# 24V_AC_SSR_Board.net
KiCad netlist of a schematic drawn in EAGLE
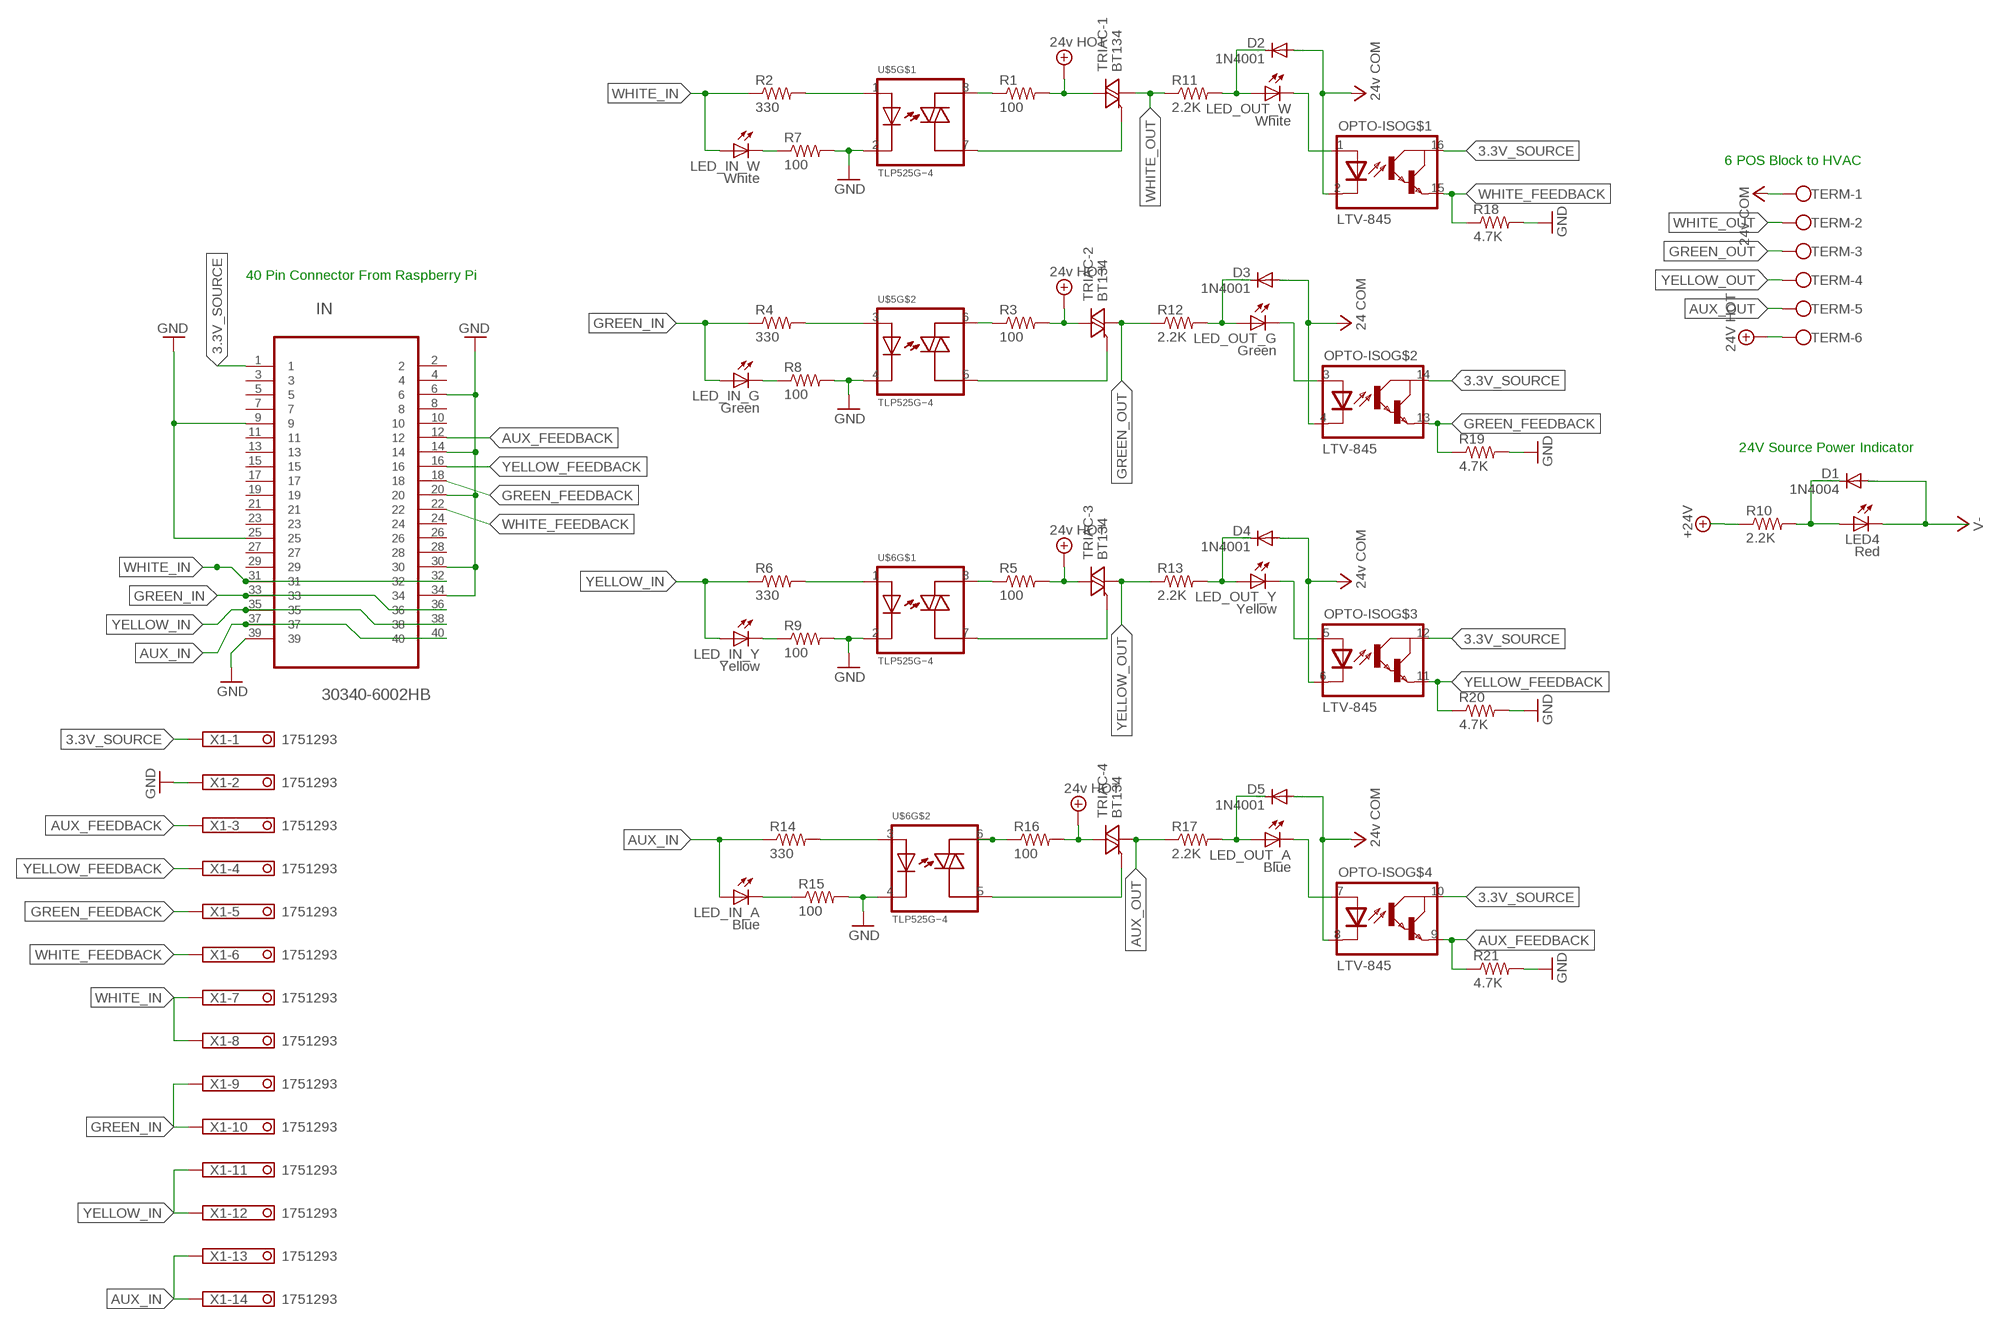
[diagram p0: schematic, sheet 1]

(export (version "E")
  (design (tool "Eeschema 10.0.6"))
  (components
    (comp (ref "D1")
      (value "1N4004")
      (footprint "eagle-import:DO41-10")
      (libsource (lib "eagle-import") (part "1N4004"))
    )
    (comp (ref "D2")
      (value "1N4001")
      (footprint "eagle-import:DO41-10")
      (libsource (lib "eagle-import") (part "1N4004"))
    )
    (comp (ref "D3")
      (value "1N4001")
      (footprint "eagle-import:DO41-10")
      (libsource (lib "eagle-import") (part "1N4004"))
    )
    (comp (ref "D4")
      (value "1N4001")
      (footprint "eagle-import:DO41-10")
      (libsource (lib "eagle-import") (part "1N4004"))
    )
    (comp (ref "D5")
      (value "1N4001")
      (footprint "eagle-import:DO41-10")
      (libsource (lib "eagle-import") (part "1N4004"))
    )
    (comp (ref "IN")
      (value "30340-6002HB")
      (footprint "eagle-import:3M_2540-6002UB")
      (fields (field (name "MPN") "2540-6002UB"))
      (libsource (lib "eagle-import") (part "2540-6002UB"))
    )
    (comp (ref "LED4")
      (value "Red")
      (footprint "eagle-import:LED3MM")
      (libsource (lib "eagle-import") (part "LED3MM"))
    )
    (comp (ref "LED_IN_A")
      (value "Blue")
      (footprint "eagle-import:LED3MM")
      (libsource (lib "eagle-import") (part "LED3MM"))
    )
    (comp (ref "LED_IN_G")
      (value "Green")
      (footprint "eagle-import:LED3MM")
      (libsource (lib "eagle-import") (part "LED3MM"))
    )
    (comp (ref "LED_IN_W")
      (value "White")
      (footprint "eagle-import:LED3MM")
      (libsource (lib "eagle-import") (part "LED3MM"))
    )
    (comp (ref "LED_IN_Y")
      (value "Yellow")
      (footprint "eagle-import:LED3MM")
      (libsource (lib "eagle-import") (part "LED3MM"))
    )
    (comp (ref "LED_OUT_A")
      (value "Blue")
      (footprint "eagle-import:LED3MM")
      (libsource (lib "eagle-import") (part "LED3MM"))
    )
    (comp (ref "LED_OUT_G")
      (value "Green")
      (footprint "eagle-import:LED3MM")
      (libsource (lib "eagle-import") (part "LED3MM"))
    )
    (comp (ref "LED_OUT_W")
      (value "White")
      (footprint "eagle-import:LED3MM")
      (libsource (lib "eagle-import") (part "LED3MM"))
    )
    (comp (ref "LED_OUT_Y")
      (value "Yellow")
      (footprint "eagle-import:LED3MM")
      (libsource (lib "eagle-import") (part "LED3MM"))
    )
    (comp (ref "OPTO-ISO")
      (value "LTV-845")
      (footprint "eagle-import:DIL16")
      (libsource (lib "eagle-import") (part "LTV-845"))
    )
    (comp (ref "R1")
      (value "100")
      (footprint "eagle-import:0204_7")
      (libsource (lib "eagle-import") (part "R-US_0204/7"))
    )
    (comp (ref "R2")
      (value "330")
      (footprint "eagle-import:0204_7")
      (libsource (lib "eagle-import") (part "R-US_0204/7"))
    )
    (comp (ref "R3")
      (value "100")
      (footprint "eagle-import:0204_7")
      (libsource (lib "eagle-import") (part "R-US_0204/7"))
    )
    (comp (ref "R4")
      (value "330")
      (footprint "eagle-import:0204_7")
      (libsource (lib "eagle-import") (part "R-US_0204/7"))
    )
    (comp (ref "R5")
      (value "100")
      (footprint "eagle-import:0204_7")
      (libsource (lib "eagle-import") (part "R-US_0204/7"))
    )
    (comp (ref "R6")
      (value "330")
      (footprint "eagle-import:0204_7")
      (libsource (lib "eagle-import") (part "R-US_0204/7"))
    )
    (comp (ref "R7")
      (value "100")
      (footprint "eagle-import:0204_7")
      (libsource (lib "eagle-import") (part "R-US_0204/7"))
    )
    (comp (ref "R8")
      (value "100")
      (footprint "eagle-import:0204_7")
      (libsource (lib "eagle-import") (part "R-US_0204/7"))
    )
    (comp (ref "R9")
      (value "100")
      (footprint "eagle-import:0204_7")
      (libsource (lib "eagle-import") (part "R-US_0204/7"))
    )
    (comp (ref "R10")
      (value "2.2K")
      (footprint "eagle-import:0204_7")
      (libsource (lib "eagle-import") (part "R-US_0204/7"))
    )
    (comp (ref "R11")
      (value "2.2K")
      (footprint "eagle-import:0204_7")
      (libsource (lib "eagle-import") (part "R-US_0204/7"))
    )
    (comp (ref "R12")
      (value "2.2K")
      (footprint "eagle-import:0204_7")
      (libsource (lib "eagle-import") (part "R-US_0204/7"))
    )
    (comp (ref "R13")
      (value "2.2K")
      (footprint "eagle-import:0204_7")
      (libsource (lib "eagle-import") (part "R-US_0204/7"))
    )
    (comp (ref "R14")
      (value "330")
      (footprint "eagle-import:0204_7")
      (libsource (lib "eagle-import") (part "R-US_0204/7"))
    )
    (comp (ref "R15")
      (value "100")
      (footprint "eagle-import:0204_7")
      (libsource (lib "eagle-import") (part "R-US_0204/7"))
    )
    (comp (ref "R16")
      (value "100")
      (footprint "eagle-import:0204_7")
      (libsource (lib "eagle-import") (part "R-US_0204/7"))
    )
    (comp (ref "R17")
      (value "2.2K")
      (footprint "eagle-import:0204_7")
      (libsource (lib "eagle-import") (part "R-US_0204/7"))
    )
    (comp (ref "R18")
      (value "4.7K")
      (footprint "eagle-import:0204_7")
      (libsource (lib "eagle-import") (part "R-US_0204/7"))
    )
    (comp (ref "R19")
      (value "4.7K")
      (footprint "eagle-import:0204_7")
      (libsource (lib "eagle-import") (part "R-US_0204/7"))
    )
    (comp (ref "R20")
      (value "4.7K")
      (footprint "eagle-import:0204_7")
      (libsource (lib "eagle-import") (part "R-US_0204/7"))
    )
    (comp (ref "R21")
      (value "4.7K")
      (footprint "eagle-import:0204_7")
      (libsource (lib "eagle-import") (part "R-US_0204/7"))
    )
    (comp (ref "TERM")
      (value "W237-6")
      (footprint "eagle-import:W237-6")
      (libsource (lib "eagle-import") (part "W237-6"))
    )
    (comp (ref "TRIAC-1")
      (value "BT134")
      (footprint "eagle-import:SOT82")
      (libsource (lib "eagle-import") (part "BT134"))
    )
    (comp (ref "TRIAC-2")
      (value "BT134")
      (footprint "eagle-import:SOT82")
      (libsource (lib "eagle-import") (part "BT134"))
    )
    (comp (ref "TRIAC-3")
      (value "BT134")
      (footprint "eagle-import:SOT82")
      (libsource (lib "eagle-import") (part "BT134"))
    )
    (comp (ref "TRIAC-4")
      (value "BT134")
      (footprint "eagle-import:SOT82")
      (libsource (lib "eagle-import") (part "BT134"))
    )
    (comp (ref "U$5")
      (value "TLP525G−4")
      (footprint "eagle-import:DIL08")
      (libsource (lib "eagle-import") (part "TLP525G−4"))
    )
    (comp (ref "U$6")
      (value "TLP525G−4")
      (footprint "eagle-import:DIL08")
      (libsource (lib "eagle-import") (part "TLP525G−4"))
    )
    (comp (ref "X1")
      (value "1751293")
      (footprint "eagle-import:1751293")
      (libsource (lib "eagle-import") (part "1751293"))
    )
  )
  (nets
    (net (code "1") (name "+24V") (class "Default")
      (node (ref "R1") (pin "2") (pinfunction "2_2") (pintype "passive"))
      (node (ref "R10") (pin "1") (pinfunction "1_1") (pintype "passive"))
      (node (ref "R16") (pin "2") (pinfunction "2_2") (pintype "passive"))
      (node (ref "R3") (pin "2") (pinfunction "2_2") (pintype "passive"))
      (node (ref "R5") (pin "2") (pinfunction "2_2") (pintype "passive"))
      (node (ref "TERM") (pin "6") (pinfunction "KL_6") (pintype "passive"))
      (node (ref "TRIAC-1") (pin "2") (pinfunction "A2_2") (pintype "passive"))
      (node (ref "TRIAC-2") (pin "2") (pinfunction "A2_2") (pintype "passive"))
      (node (ref "TRIAC-3") (pin "2") (pinfunction "A2_2") (pintype "passive"))
      (node (ref "TRIAC-4") (pin "2") (pinfunction "A2_2") (pintype "passive"))
    )
    (net (code "2") (name "3.3V_SOURCE") (class "Default")
      (node (ref "IN") (pin "1") (pinfunction "1_1") (pintype "passive"))
      (node (ref "OPTO-ISO") (pin "10") (pinfunction "COLLECTOR_10") (pintype "bidirectional"))
      (node (ref "OPTO-ISO") (pin "12") (pinfunction "COLLECTOR_12") (pintype "bidirectional"))
      (node (ref "OPTO-ISO") (pin "14") (pinfunction "COLLECTOR_14") (pintype "bidirectional"))
      (node (ref "OPTO-ISO") (pin "16") (pinfunction "COLLECTOR_16") (pintype "bidirectional"))
      (node (ref "X1") (pin "1") (pinfunction "K_1") (pintype "passive"))
    )
    (net (code "3") (name "24 COM") (class "Default")
      (node (ref "D1") (pin "A") (pinfunction "A_A") (pintype "passive"))
      (node (ref "D2") (pin "A") (pinfunction "A_A") (pintype "passive"))
      (node (ref "D3") (pin "A") (pinfunction "A_A") (pintype "passive"))
      (node (ref "D4") (pin "A") (pinfunction "A_A") (pintype "passive"))
      (node (ref "D5") (pin "A") (pinfunction "A_A") (pintype "passive"))
      (node (ref "LED4") (pin "K") (pinfunction "C_K") (pintype "passive"))
      (node (ref "OPTO-ISO") (pin "2") (pinfunction "CATHODE_2") (pintype "bidirectional"))
      (node (ref "OPTO-ISO") (pin "4") (pinfunction "CATHODE_4") (pintype "bidirectional"))
      (node (ref "OPTO-ISO") (pin "6") (pinfunction "CATHODE_6") (pintype "bidirectional"))
      (node (ref "OPTO-ISO") (pin "8") (pinfunction "CATHODE_8") (pintype "bidirectional"))
      (node (ref "TERM") (pin "1") (pinfunction "KL_1") (pintype "passive"))
    )
    (net (code "4") (name "AUX_FEEDBACK") (class "Default")
      (node (ref "IN") (pin "12") (pinfunction "12_12") (pintype "passive"))
      (node (ref "OPTO-ISO") (pin "9") (pinfunction "EMITTER_9") (pintype "bidirectional"))
      (node (ref "R21") (pin "1") (pinfunction "1_1") (pintype "passive"))
      (node (ref "X1") (pin "3") (pinfunction "K_3") (pintype "passive"))
    )
    (net (code "5") (name "AUX_IN") (class "Default")
      (node (ref "IN") (pin "37") (pinfunction "37_37") (pintype "passive"))
      (node (ref "IN") (pin "40") (pinfunction "40_40") (pintype "passive"))
      (node (ref "LED_IN_A") (pin "A") (pinfunction "A_A") (pintype "passive"))
      (node (ref "R14") (pin "1") (pinfunction "1_1") (pintype "passive"))
      (node (ref "X1") (pin "13") (pinfunction "K_13") (pintype "passive"))
      (node (ref "X1") (pin "14") (pinfunction "K_14") (pintype "passive"))
    )
    (net (code "6") (name "AUX_OUT") (class "Default")
      (node (ref "R17") (pin "1") (pinfunction "1_1") (pintype "passive"))
      (node (ref "TERM") (pin "5") (pinfunction "KL_5") (pintype "passive"))
      (node (ref "TRIAC-4") (pin "1") (pinfunction "A1_1") (pintype "passive"))
    )
    (net (code "7") (name "GND") (class "Default")
      (node (ref "IN") (pin "14") (pinfunction "14_14") (pintype "passive"))
      (node (ref "IN") (pin "20") (pinfunction "20_20") (pintype "passive"))
      (node (ref "IN") (pin "25") (pinfunction "25_25") (pintype "passive"))
      (node (ref "IN") (pin "30") (pinfunction "30_30") (pintype "passive"))
      (node (ref "IN") (pin "34") (pinfunction "34_34") (pintype "passive"))
      (node (ref "IN") (pin "39") (pinfunction "39_39") (pintype "passive"))
      (node (ref "IN") (pin "6") (pinfunction "6_6") (pintype "passive"))
      (node (ref "IN") (pin "9") (pinfunction "9_9") (pintype "passive"))
      (node (ref "R15") (pin "2") (pinfunction "2_2") (pintype "passive"))
      (node (ref "R18") (pin "2") (pinfunction "2_2") (pintype "passive"))
      (node (ref "R19") (pin "2") (pinfunction "2_2") (pintype "passive"))
      (node (ref "R20") (pin "2") (pinfunction "2_2") (pintype "passive"))
      (node (ref "R21") (pin "2") (pinfunction "2_2") (pintype "passive"))
      (node (ref "R7") (pin "2") (pinfunction "2_2") (pintype "passive"))
      (node (ref "R8") (pin "2") (pinfunction "2_2") (pintype "passive"))
      (node (ref "R9") (pin "2") (pinfunction "2_2") (pintype "passive"))
      (node (ref "U$5") (pin "2") (pinfunction "CATHODE_2") (pintype "bidirectional"))
      (node (ref "U$5") (pin "4") (pinfunction "CATHODE_4") (pintype "bidirectional"))
      (node (ref "U$6") (pin "2") (pinfunction "CATHODE_2") (pintype "bidirectional"))
      (node (ref "U$6") (pin "4") (pinfunction "CATHODE_4") (pintype "bidirectional"))
      (node (ref "X1") (pin "2") (pinfunction "K_2") (pintype "passive"))
    )
    (net (code "8") (name "GREEN_FEEDBACK") (class "Default")
      (node (ref "IN") (pin "18") (pinfunction "18_18") (pintype "passive"))
      (node (ref "OPTO-ISO") (pin "13") (pinfunction "EMITTER_13") (pintype "bidirectional"))
      (node (ref "R19") (pin "1") (pinfunction "1_1") (pintype "passive"))
      (node (ref "X1") (pin "5") (pinfunction "K_5") (pintype "passive"))
    )
    (net (code "9") (name "GREEN_IN") (class "Default")
      (node (ref "IN") (pin "33") (pinfunction "33_33") (pintype "passive"))
      (node (ref "IN") (pin "36") (pinfunction "36_36") (pintype "passive"))
      (node (ref "LED_IN_G") (pin "A") (pinfunction "A_A") (pintype "passive"))
      (node (ref "R4") (pin "1") (pinfunction "1_1") (pintype "passive"))
      (node (ref "X1") (pin "10") (pinfunction "K_10") (pintype "passive"))
      (node (ref "X1") (pin "9") (pinfunction "K_9") (pintype "passive"))
    )
    (net (code "10") (name "GREEN_OUT") (class "Default")
      (node (ref "R12") (pin "1") (pinfunction "1_1") (pintype "passive"))
      (node (ref "TERM") (pin "3") (pinfunction "KL_3") (pintype "passive"))
      (node (ref "TRIAC-2") (pin "1") (pinfunction "A1_1") (pintype "passive"))
    )
    (net (code "11") (name "Net-(D1-PadC)") (class "Default")
      (node (ref "D1") (pin "C") (pinfunction "C_C") (pintype "passive"))
      (node (ref "LED4") (pin "A") (pinfunction "A_A") (pintype "passive"))
      (node (ref "R10") (pin "2") (pinfunction "2_2") (pintype "passive"))
    )
    (net (code "12") (name "Net-(D2-PadC)") (class "Default")
      (node (ref "D2") (pin "C") (pinfunction "C_C") (pintype "passive"))
      (node (ref "LED_OUT_W") (pin "A") (pinfunction "A_A") (pintype "passive"))
      (node (ref "R11") (pin "2") (pinfunction "2_2") (pintype "passive"))
    )
    (net (code "13") (name "Net-(D3-PadC)") (class "Default")
      (node (ref "D3") (pin "C") (pinfunction "C_C") (pintype "passive"))
      (node (ref "LED_OUT_G") (pin "A") (pinfunction "A_A") (pintype "passive"))
      (node (ref "R12") (pin "2") (pinfunction "2_2") (pintype "passive"))
    )
    (net (code "14") (name "Net-(D4-PadC)") (class "Default")
      (node (ref "D4") (pin "C") (pinfunction "C_C") (pintype "passive"))
      (node (ref "LED_OUT_Y") (pin "A") (pinfunction "A_A") (pintype "passive"))
      (node (ref "R13") (pin "2") (pinfunction "2_2") (pintype "passive"))
    )
    (net (code "15") (name "Net-(D5-PadC)") (class "Default")
      (node (ref "D5") (pin "C") (pinfunction "C_C") (pintype "passive"))
      (node (ref "LED_OUT_A") (pin "A") (pinfunction "A_A") (pintype "passive"))
      (node (ref "R17") (pin "2") (pinfunction "2_2") (pintype "passive"))
    )
    (net (code "16") (name "Net-(LED_IN_A-C)") (class "Default")
      (node (ref "LED_IN_A") (pin "K") (pinfunction "C_K") (pintype "passive"))
      (node (ref "R15") (pin "1") (pinfunction "1_1") (pintype "passive"))
    )
    (net (code "17") (name "Net-(LED_IN_G-C)") (class "Default")
      (node (ref "LED_IN_G") (pin "K") (pinfunction "C_K") (pintype "passive"))
      (node (ref "R8") (pin "1") (pinfunction "1_1") (pintype "passive"))
    )
    (net (code "18") (name "Net-(LED_IN_W-C)") (class "Default")
      (node (ref "LED_IN_W") (pin "K") (pinfunction "C_K") (pintype "passive"))
      (node (ref "R7") (pin "1") (pinfunction "1_1") (pintype "passive"))
    )
    (net (code "19") (name "Net-(LED_IN_Y-C)") (class "Default")
      (node (ref "LED_IN_Y") (pin "K") (pinfunction "C_K") (pintype "passive"))
      (node (ref "R9") (pin "1") (pinfunction "1_1") (pintype "passive"))
    )
    (net (code "20") (name "Net-(LED_OUT_A-C)") (class "Default")
      (node (ref "LED_OUT_A") (pin "K") (pinfunction "C_K") (pintype "passive"))
      (node (ref "OPTO-ISO") (pin "7") (pinfunction "ANNODE_7") (pintype "bidirectional"))
    )
    (net (code "21") (name "Net-(LED_OUT_G-C)") (class "Default")
      (node (ref "LED_OUT_G") (pin "K") (pinfunction "C_K") (pintype "passive"))
      (node (ref "OPTO-ISO") (pin "3") (pinfunction "ANNODE_3") (pintype "bidirectional"))
    )
    (net (code "22") (name "Net-(LED_OUT_W-C)") (class "Default")
      (node (ref "LED_OUT_W") (pin "K") (pinfunction "C_K") (pintype "passive"))
      (node (ref "OPTO-ISO") (pin "1") (pinfunction "ANNODE_1") (pintype "bidirectional"))
    )
    (net (code "23") (name "Net-(LED_OUT_Y-C)") (class "Default")
      (node (ref "LED_OUT_Y") (pin "K") (pinfunction "C_K") (pintype "passive"))
      (node (ref "OPTO-ISO") (pin "5") (pinfunction "ANNODE_5") (pintype "bidirectional"))
    )
    (net (code "24") (name "Net-(TRIAC-1-G)") (class "Default")
      (node (ref "TRIAC-1") (pin "3") (pinfunction "G_3") (pintype "passive"))
      (node (ref "U$5") (pin "7") (pinfunction "T1_7") (pintype "bidirectional"))
    )
    (net (code "25") (name "Net-(TRIAC-2-G)") (class "Default")
      (node (ref "TRIAC-2") (pin "3") (pinfunction "G_3") (pintype "passive"))
      (node (ref "U$5") (pin "5") (pinfunction "T1_5") (pintype "bidirectional"))
    )
    (net (code "26") (name "Net-(TRIAC-3-G)") (class "Default")
      (node (ref "TRIAC-3") (pin "3") (pinfunction "G_3") (pintype "passive"))
      (node (ref "U$6") (pin "7") (pinfunction "T1_7") (pintype "bidirectional"))
    )
    (net (code "27") (name "Net-(TRIAC-4-G)") (class "Default")
      (node (ref "TRIAC-4") (pin "3") (pinfunction "G_3") (pintype "passive"))
      (node (ref "U$6") (pin "5") (pinfunction "T1_5") (pintype "bidirectional"))
    )
    (net (code "28") (name "Net-(U$5A-ANNODE)") (class "Default")
      (node (ref "R2") (pin "2") (pinfunction "2_2") (pintype "passive"))
      (node (ref "U$5") (pin "1") (pinfunction "ANNODE_1") (pintype "bidirectional"))
    )
    (net (code "29") (name "Net-(U$5A-T2)") (class "Default")
      (node (ref "R1") (pin "1") (pinfunction "1_1") (pintype "passive"))
      (node (ref "U$5") (pin "8") (pinfunction "T2_8") (pintype "bidirectional"))
    )
    (net (code "30") (name "Net-(U$5B-ANNODE)") (class "Default")
      (node (ref "R4") (pin "2") (pinfunction "2_2") (pintype "passive"))
      (node (ref "U$5") (pin "3") (pinfunction "ANNODE_3") (pintype "bidirectional"))
    )
    (net (code "31") (name "Net-(U$5B-T2)") (class "Default")
      (node (ref "R3") (pin "1") (pinfunction "1_1") (pintype "passive"))
      (node (ref "U$5") (pin "6") (pinfunction "T2_6") (pintype "bidirectional"))
    )
    (net (code "32") (name "Net-(U$6A-ANNODE)") (class "Default")
      (node (ref "R6") (pin "2") (pinfunction "2_2") (pintype "passive"))
      (node (ref "U$6") (pin "1") (pinfunction "ANNODE_1") (pintype "bidirectional"))
    )
    (net (code "33") (name "Net-(U$6A-T2)") (class "Default")
      (node (ref "R5") (pin "1") (pinfunction "1_1") (pintype "passive"))
      (node (ref "U$6") (pin "8") (pinfunction "T2_8") (pintype "bidirectional"))
    )
    (net (code "34") (name "Net-(U$6B-ANNODE)") (class "Default")
      (node (ref "R14") (pin "2") (pinfunction "2_2") (pintype "passive"))
      (node (ref "U$6") (pin "3") (pinfunction "ANNODE_3") (pintype "bidirectional"))
    )
    (net (code "35") (name "Net-(U$6B-T2)") (class "Default")
      (node (ref "R16") (pin "1") (pinfunction "1_1") (pintype "passive"))
      (node (ref "U$6") (pin "6") (pinfunction "T2_6") (pintype "bidirectional"))
    )
    (net (code "36") (name "WHITE_FEEDBACK") (class "Default")
      (node (ref "IN") (pin "22") (pinfunction "22_22") (pintype "passive"))
      (node (ref "OPTO-ISO") (pin "15") (pinfunction "EMITTER_15") (pintype "bidirectional"))
      (node (ref "R18") (pin "1") (pinfunction "1_1") (pintype "passive"))
      (node (ref "X1") (pin "6") (pinfunction "K_6") (pintype "passive"))
    )
    (net (code "37") (name "WHITE_IN") (class "Default")
      (node (ref "IN") (pin "31") (pinfunction "31_31") (pintype "passive"))
      (node (ref "IN") (pin "32") (pinfunction "32_32") (pintype "passive"))
      (node (ref "LED_IN_W") (pin "A") (pinfunction "A_A") (pintype "passive"))
      (node (ref "R2") (pin "1") (pinfunction "1_1") (pintype "passive"))
      (node (ref "X1") (pin "7") (pinfunction "K_7") (pintype "passive"))
      (node (ref "X1") (pin "8") (pinfunction "K_8") (pintype "passive"))
    )
    (net (code "38") (name "WHITE_OUT") (class "Default")
      (node (ref "R11") (pin "1") (pinfunction "1_1") (pintype "passive"))
      (node (ref "TERM") (pin "2") (pinfunction "KL_2") (pintype "passive"))
      (node (ref "TRIAC-1") (pin "1") (pinfunction "A1_1") (pintype "passive"))
    )
    (net (code "39") (name "YELLOW_FEEDBACK") (class "Default")
      (node (ref "IN") (pin "16") (pinfunction "16_16") (pintype "passive"))
      (node (ref "OPTO-ISO") (pin "11") (pinfunction "EMITTER_11") (pintype "bidirectional"))
      (node (ref "R20") (pin "1") (pinfunction "1_1") (pintype "passive"))
      (node (ref "X1") (pin "4") (pinfunction "K_4") (pintype "passive"))
    )
    (net (code "40") (name "YELLOW_IN") (class "Default")
      (node (ref "IN") (pin "35") (pinfunction "35_35") (pintype "passive"))
      (node (ref "IN") (pin "38") (pinfunction "38_38") (pintype "passive"))
      (node (ref "LED_IN_Y") (pin "A") (pinfunction "A_A") (pintype "passive"))
      (node (ref "R6") (pin "1") (pinfunction "1_1") (pintype "passive"))
      (node (ref "X1") (pin "11") (pinfunction "K_11") (pintype "passive"))
      (node (ref "X1") (pin "12") (pinfunction "K_12") (pintype "passive"))
    )
    (net (code "41") (name "YELLOW_OUT") (class "Default")
      (node (ref "R13") (pin "1") (pinfunction "1_1") (pintype "passive"))
      (node (ref "TERM") (pin "4") (pinfunction "KL_4") (pintype "passive"))
      (node (ref "TRIAC-3") (pin "1") (pinfunction "A1_1") (pintype "passive"))
    )
    (net (code "42") (name "unconnected-(IN-Pad2)") (class "Default")
      (node (ref "IN") (pin "2") (pinfunction "2_2") (pintype "passive"))
    )
    (net (code "43") (name "unconnected-(IN-Pad3)") (class "Default")
      (node (ref "IN") (pin "3") (pinfunction "3_3") (pintype "passive"))
    )
    (net (code "44") (name "unconnected-(IN-Pad4)") (class "Default")
      (node (ref "IN") (pin "4") (pinfunction "4_4") (pintype "passive"))
    )
    (net (code "45") (name "unconnected-(IN-Pad5)") (class "Default")
      (node (ref "IN") (pin "5") (pinfunction "5_5") (pintype "passive"))
    )
    (net (code "46") (name "unconnected-(IN-Pad7)") (class "Default")
      (node (ref "IN") (pin "7") (pinfunction "7_7") (pintype "passive"))
    )
    (net (code "47") (name "unconnected-(IN-Pad8)") (class "Default")
      (node (ref "IN") (pin "8") (pinfunction "8_8") (pintype "passive"))
    )
    (net (code "48") (name "unconnected-(IN-Pad10)") (class "Default")
      (node (ref "IN") (pin "10") (pinfunction "10_10") (pintype "passive"))
    )
    (net (code "49") (name "unconnected-(IN-Pad11)") (class "Default")
      (node (ref "IN") (pin "11") (pinfunction "11_11") (pintype "passive"))
    )
    (net (code "50") (name "unconnected-(IN-Pad13)") (class "Default")
      (node (ref "IN") (pin "13") (pinfunction "13_13") (pintype "passive"))
    )
    (net (code "51") (name "unconnected-(IN-Pad15)") (class "Default")
      (node (ref "IN") (pin "15") (pinfunction "15_15") (pintype "passive"))
    )
    (net (code "52") (name "unconnected-(IN-Pad17)") (class "Default")
      (node (ref "IN") (pin "17") (pinfunction "17_17") (pintype "passive"))
    )
    (net (code "53") (name "unconnected-(IN-Pad19)") (class "Default")
      (node (ref "IN") (pin "19") (pinfunction "19_19") (pintype "passive"))
    )
    (net (code "54") (name "unconnected-(IN-Pad21)") (class "Default")
      (node (ref "IN") (pin "21") (pinfunction "21_21") (pintype "passive"))
    )
    (net (code "55") (name "unconnected-(IN-Pad23)") (class "Default")
      (node (ref "IN") (pin "23") (pinfunction "23_23") (pintype "passive"))
    )
    (net (code "56") (name "unconnected-(IN-Pad24)") (class "Default")
      (node (ref "IN") (pin "24") (pinfunction "24_24") (pintype "passive"))
    )
    (net (code "57") (name "unconnected-(IN-Pad26)") (class "Default")
      (node (ref "IN") (pin "26") (pinfunction "26_26") (pintype "passive"))
    )
    (net (code "58") (name "unconnected-(IN-Pad27)") (class "Default")
      (node (ref "IN") (pin "27") (pinfunction "27_27") (pintype "passive"))
    )
    (net (code "59") (name "unconnected-(IN-Pad28)") (class "Default")
      (node (ref "IN") (pin "28") (pinfunction "28_28") (pintype "passive"))
    )
    (net (code "60") (name "unconnected-(IN-Pad29)") (class "Default")
      (node (ref "IN") (pin "29") (pinfunction "29_29") (pintype "passive"))
    )
  )
)
